# unoedge.net
KiCad netlist of a schematic drawn in EAGLE
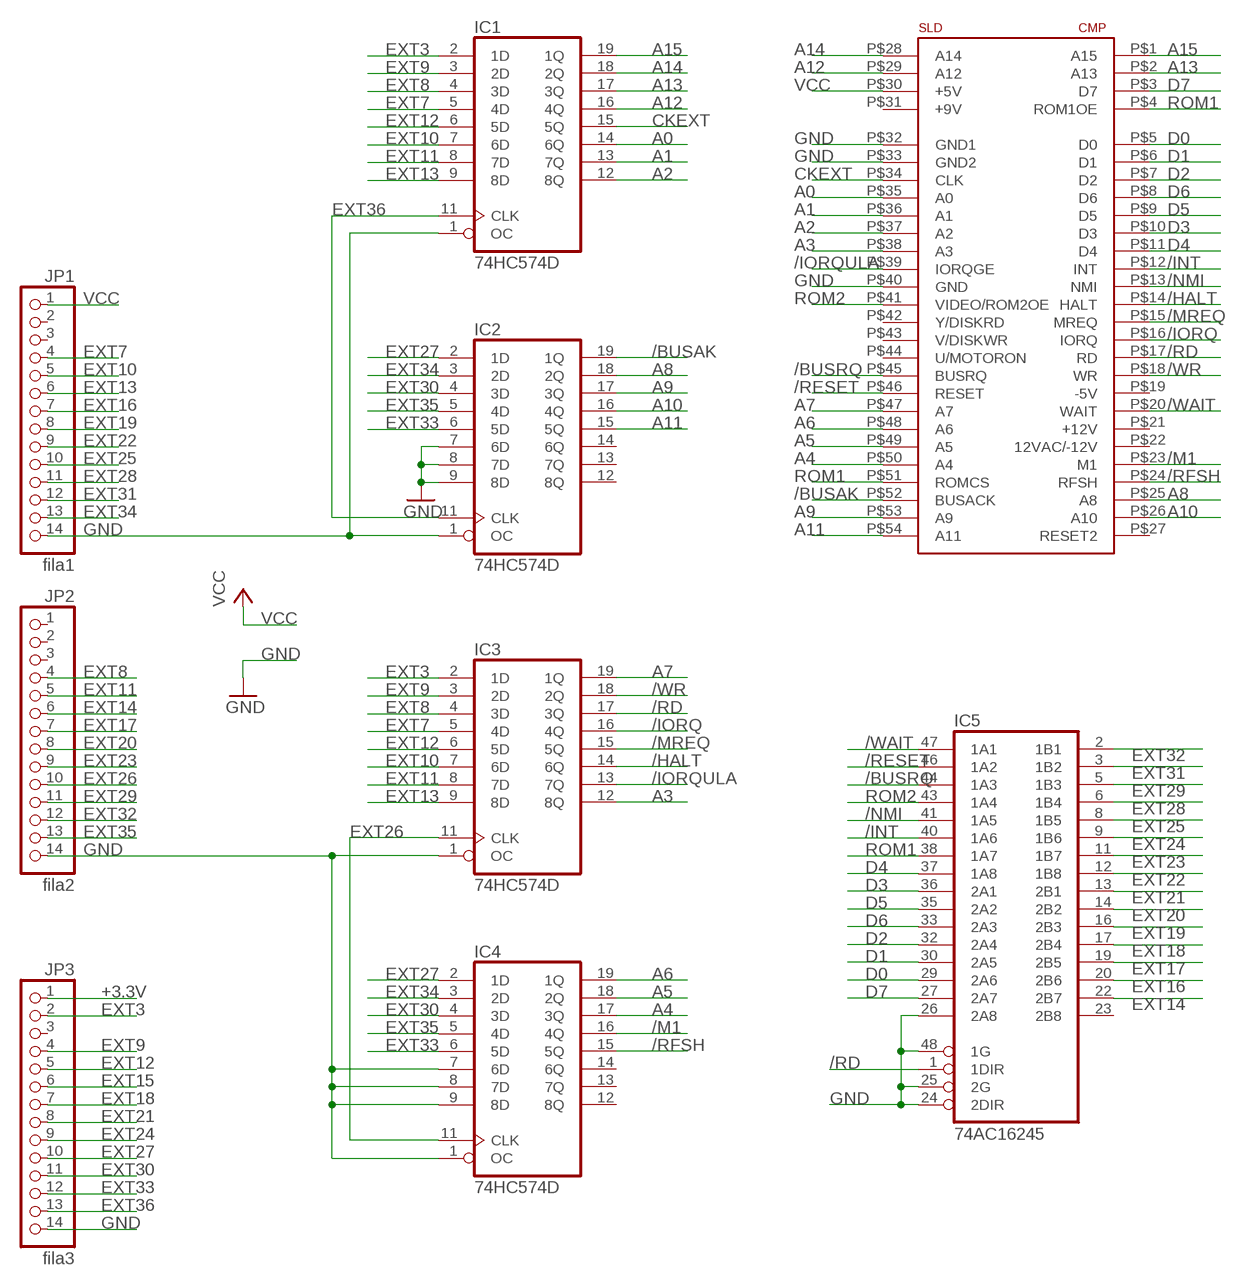
[diagram p0: schematic, sheet 1]

(export (version "E")
  (design (tool "Eeschema 10.0.6"))
  (components
    (comp (ref "IC1")
      (value "74HC574D")
      (footprint "eagle-import:SO20W")
      (libsource (lib "eagle-import") (part "74574DHC"))
    )
    (comp (ref "IC2")
      (value "74HC574D")
      (footprint "eagle-import:SO20W")
      (libsource (lib "eagle-import") (part "74574DHC"))
    )
    (comp (ref "IC3")
      (value "74HC574D")
      (footprint "eagle-import:SO20W")
      (libsource (lib "eagle-import") (part "74574DHC"))
    )
    (comp (ref "IC4")
      (value "74HC574D")
      (footprint "eagle-import:SO20W")
      (libsource (lib "eagle-import") (part "74574DHC"))
    )
    (comp (ref "IC5")
      (value "74AC16245")
      (footprint "eagle-import:SSOP48DL")
      (libsource (lib "eagle-import") (part "74AC16245"))
    )
    (comp (ref "JP1")
      (value "fila1")
      (footprint "eagle-import:1X14")
      (libsource (lib "eagle-import") (part "PINHD-1X14"))
    )
    (comp (ref "JP2")
      (value "fila2")
      (footprint "eagle-import:1X14")
      (libsource (lib "eagle-import") (part "PINHD-1X14"))
    )
    (comp (ref "JP3")
      (value "fila3")
      (footprint "eagle-import:1X14")
      (libsource (lib "eagle-import") (part "PINHD-1X14"))
    )
    (comp (ref "U$2")
      (value "CONECTOR_EDGE_LADO_SPECTRUM")
      (footprint "eagle-import:CONECTOR_LADO_SPECTRUM")
      (libsource (lib "eagle-import") (part "CONECTOR_EDGE_LADO_SPECTRUM"))
    )
  )
  (nets
    (net (code "1") (name "/+3.3V") (class "Default")
      (node (ref "JP3") (pin "1") (pinfunction "1_1") (pintype "passive"))
    )
    (net (code "2") (name "/A0") (class "Default")
      (node (ref "IC1") (pin "14") (pinfunction "6Q_14") (pintype "tri_state"))
      (node (ref "U$2") (pin "P$35") (pinfunction "A0_P$35") (pintype "bidirectional"))
    )
    (net (code "3") (name "/A1") (class "Default")
      (node (ref "IC1") (pin "13") (pinfunction "7Q_13") (pintype "tri_state"))
      (node (ref "U$2") (pin "P$36") (pinfunction "A1_P$36") (pintype "bidirectional"))
    )
    (net (code "4") (name "/A2") (class "Default")
      (node (ref "IC1") (pin "12") (pinfunction "8Q_12") (pintype "tri_state"))
      (node (ref "U$2") (pin "P$37") (pinfunction "A2_P$37") (pintype "bidirectional"))
    )
    (net (code "5") (name "/A3") (class "Default")
      (node (ref "IC3") (pin "12") (pinfunction "8Q_12") (pintype "tri_state"))
      (node (ref "U$2") (pin "P$38") (pinfunction "A3_P$38") (pintype "bidirectional"))
    )
    (net (code "6") (name "/A4") (class "Default")
      (node (ref "IC4") (pin "17") (pinfunction "3Q_17") (pintype "tri_state"))
      (node (ref "U$2") (pin "P$50") (pinfunction "A4_P$50") (pintype "bidirectional"))
    )
    (net (code "7") (name "/A5") (class "Default")
      (node (ref "IC4") (pin "18") (pinfunction "2Q_18") (pintype "tri_state"))
      (node (ref "U$2") (pin "P$49") (pinfunction "A5_P$49") (pintype "bidirectional"))
    )
    (net (code "8") (name "/A6") (class "Default")
      (node (ref "IC4") (pin "19") (pinfunction "1Q_19") (pintype "tri_state"))
      (node (ref "U$2") (pin "P$48") (pinfunction "A6_P$48") (pintype "bidirectional"))
    )
    (net (code "9") (name "/A7") (class "Default")
      (node (ref "IC3") (pin "19") (pinfunction "1Q_19") (pintype "tri_state"))
      (node (ref "U$2") (pin "P$47") (pinfunction "A7_P$47") (pintype "bidirectional"))
    )
    (net (code "10") (name "/A8") (class "Default")
      (node (ref "IC2") (pin "18") (pinfunction "2Q_18") (pintype "tri_state"))
      (node (ref "U$2") (pin "P$25") (pinfunction "A8_P$25") (pintype "bidirectional"))
    )
    (net (code "11") (name "/A9") (class "Default")
      (node (ref "IC2") (pin "17") (pinfunction "3Q_17") (pintype "tri_state"))
      (node (ref "U$2") (pin "P$53") (pinfunction "A9_P$53") (pintype "bidirectional"))
    )
    (net (code "12") (name "/A10") (class "Default")
      (node (ref "IC2") (pin "16") (pinfunction "4Q_16") (pintype "tri_state"))
      (node (ref "U$2") (pin "P$26") (pinfunction "A10_P$26") (pintype "bidirectional"))
    )
    (net (code "13") (name "/A11") (class "Default")
      (node (ref "IC2") (pin "15") (pinfunction "5Q_15") (pintype "tri_state"))
      (node (ref "U$2") (pin "P$54") (pinfunction "A11_P$54") (pintype "bidirectional"))
    )
    (net (code "14") (name "/A12") (class "Default")
      (node (ref "IC1") (pin "16") (pinfunction "4Q_16") (pintype "tri_state"))
      (node (ref "U$2") (pin "P$29") (pinfunction "A12_P$29") (pintype "bidirectional"))
    )
    (net (code "15") (name "/A13") (class "Default")
      (node (ref "IC1") (pin "17") (pinfunction "3Q_17") (pintype "tri_state"))
      (node (ref "U$2") (pin "P$2") (pinfunction "A13_P$2") (pintype "bidirectional"))
    )
    (net (code "16") (name "/A14") (class "Default")
      (node (ref "IC1") (pin "18") (pinfunction "2Q_18") (pintype "tri_state"))
      (node (ref "U$2") (pin "P$28") (pinfunction "A14_P$28") (pintype "bidirectional"))
    )
    (net (code "17") (name "/A15") (class "Default")
      (node (ref "IC1") (pin "19") (pinfunction "1Q_19") (pintype "tri_state"))
      (node (ref "U$2") (pin "P$1") (pinfunction "A15_P$1") (pintype "bidirectional"))
    )
    (net (code "18") (name "/CKEXT") (class "Default")
      (node (ref "IC1") (pin "15") (pinfunction "5Q_15") (pintype "tri_state"))
      (node (ref "U$2") (pin "P$34") (pinfunction "CLK_P$34") (pintype "bidirectional"))
    )
    (net (code "19") (name "/D0") (class "Default")
      (node (ref "IC5") (pin "29") (pinfunction "2A6_29") (pintype "bidirectional"))
      (node (ref "U$2") (pin "P$5") (pinfunction "D0_P$5") (pintype "bidirectional"))
    )
    (net (code "20") (name "/D1") (class "Default")
      (node (ref "IC5") (pin "30") (pinfunction "2A5_30") (pintype "bidirectional"))
      (node (ref "U$2") (pin "P$6") (pinfunction "D1_P$6") (pintype "bidirectional"))
    )
    (net (code "21") (name "/D2") (class "Default")
      (node (ref "IC5") (pin "32") (pinfunction "2A4_32") (pintype "bidirectional"))
      (node (ref "U$2") (pin "P$7") (pinfunction "D2_P$7") (pintype "bidirectional"))
    )
    (net (code "22") (name "/D3") (class "Default")
      (node (ref "IC5") (pin "36") (pinfunction "2A1_36") (pintype "bidirectional"))
      (node (ref "U$2") (pin "P$10") (pinfunction "D3_P$10") (pintype "bidirectional"))
    )
    (net (code "23") (name "/D4") (class "Default")
      (node (ref "IC5") (pin "37") (pinfunction "1A8_37") (pintype "bidirectional"))
      (node (ref "U$2") (pin "P$11") (pinfunction "D4_P$11") (pintype "bidirectional"))
    )
    (net (code "24") (name "/D5") (class "Default")
      (node (ref "IC5") (pin "35") (pinfunction "2A2_35") (pintype "bidirectional"))
      (node (ref "U$2") (pin "P$9") (pinfunction "D5_P$9") (pintype "bidirectional"))
    )
    (net (code "25") (name "/D6") (class "Default")
      (node (ref "IC5") (pin "33") (pinfunction "2A3_33") (pintype "bidirectional"))
      (node (ref "U$2") (pin "P$8") (pinfunction "D6_P$8") (pintype "bidirectional"))
    )
    (net (code "26") (name "/D7") (class "Default")
      (node (ref "IC5") (pin "27") (pinfunction "2A7_27") (pintype "bidirectional"))
      (node (ref "U$2") (pin "P$3") (pinfunction "D7_P$3") (pintype "bidirectional"))
    )
    (net (code "27") (name "/EXT3") (class "Default")
      (node (ref "IC1") (pin "2") (pinfunction "1D_2") (pintype "input"))
      (node (ref "IC3") (pin "2") (pinfunction "1D_2") (pintype "input"))
      (node (ref "JP3") (pin "2") (pinfunction "2_2") (pintype "passive"))
    )
    (net (code "28") (name "/EXT7") (class "Default")
      (node (ref "IC1") (pin "5") (pinfunction "4D_5") (pintype "input"))
      (node (ref "IC3") (pin "5") (pinfunction "4D_5") (pintype "input"))
      (node (ref "JP1") (pin "4") (pinfunction "4_4") (pintype "passive"))
    )
    (net (code "29") (name "/EXT8") (class "Default")
      (node (ref "IC1") (pin "4") (pinfunction "3D_4") (pintype "input"))
      (node (ref "IC3") (pin "4") (pinfunction "3D_4") (pintype "input"))
      (node (ref "JP2") (pin "4") (pinfunction "4_4") (pintype "passive"))
    )
    (net (code "30") (name "/EXT9") (class "Default")
      (node (ref "IC1") (pin "3") (pinfunction "2D_3") (pintype "input"))
      (node (ref "IC3") (pin "3") (pinfunction "2D_3") (pintype "input"))
      (node (ref "JP3") (pin "4") (pinfunction "4_4") (pintype "passive"))
    )
    (net (code "31") (name "/EXT10") (class "Default")
      (node (ref "IC1") (pin "7") (pinfunction "6D_7") (pintype "input"))
      (node (ref "IC3") (pin "7") (pinfunction "6D_7") (pintype "input"))
      (node (ref "JP1") (pin "5") (pinfunction "5_5") (pintype "passive"))
    )
    (net (code "32") (name "/EXT11") (class "Default")
      (node (ref "IC1") (pin "8") (pinfunction "7D_8") (pintype "input"))
      (node (ref "IC3") (pin "8") (pinfunction "7D_8") (pintype "input"))
      (node (ref "JP2") (pin "5") (pinfunction "5_5") (pintype "passive"))
    )
    (net (code "33") (name "/EXT12") (class "Default")
      (node (ref "IC1") (pin "6") (pinfunction "5D_6") (pintype "input"))
      (node (ref "IC3") (pin "6") (pinfunction "5D_6") (pintype "input"))
      (node (ref "JP3") (pin "5") (pinfunction "5_5") (pintype "passive"))
    )
    (net (code "34") (name "/EXT13") (class "Default")
      (node (ref "IC1") (pin "9") (pinfunction "8D_9") (pintype "input"))
      (node (ref "IC3") (pin "9") (pinfunction "8D_9") (pintype "input"))
      (node (ref "JP1") (pin "6") (pinfunction "6_6") (pintype "passive"))
    )
    (net (code "35") (name "/EXT14") (class "Default")
      (node (ref "IC5") (pin "22") (pinfunction "2B7_22") (pintype "bidirectional"))
      (node (ref "JP2") (pin "6") (pinfunction "6_6") (pintype "passive"))
    )
    (net (code "36") (name "/EXT15") (class "Default")
      (node (ref "JP3") (pin "6") (pinfunction "6_6") (pintype "passive"))
    )
    (net (code "37") (name "/EXT16") (class "Default")
      (node (ref "IC5") (pin "20") (pinfunction "2B6_20") (pintype "bidirectional"))
      (node (ref "JP1") (pin "7") (pinfunction "7_7") (pintype "passive"))
    )
    (net (code "38") (name "/EXT17") (class "Default")
      (node (ref "IC5") (pin "19") (pinfunction "2B5_19") (pintype "bidirectional"))
      (node (ref "JP2") (pin "7") (pinfunction "7_7") (pintype "passive"))
    )
    (net (code "39") (name "/EXT18") (class "Default")
      (node (ref "IC5") (pin "17") (pinfunction "2B4_17") (pintype "bidirectional"))
      (node (ref "JP3") (pin "7") (pinfunction "7_7") (pintype "passive"))
    )
    (net (code "40") (name "/EXT19") (class "Default")
      (node (ref "IC5") (pin "16") (pinfunction "2B3_16") (pintype "bidirectional"))
      (node (ref "JP1") (pin "8") (pinfunction "8_8") (pintype "passive"))
    )
    (net (code "41") (name "/EXT20") (class "Default")
      (node (ref "IC5") (pin "14") (pinfunction "2B2_14") (pintype "bidirectional"))
      (node (ref "JP2") (pin "8") (pinfunction "8_8") (pintype "passive"))
    )
    (net (code "42") (name "/EXT21") (class "Default")
      (node (ref "IC5") (pin "13") (pinfunction "2B1_13") (pintype "bidirectional"))
      (node (ref "JP3") (pin "8") (pinfunction "8_8") (pintype "passive"))
    )
    (net (code "43") (name "/EXT22") (class "Default")
      (node (ref "IC5") (pin "12") (pinfunction "1B8_12") (pintype "bidirectional"))
      (node (ref "JP1") (pin "9") (pinfunction "9_9") (pintype "passive"))
    )
    (net (code "44") (name "/EXT23") (class "Default")
      (node (ref "IC5") (pin "11") (pinfunction "1B7_11") (pintype "bidirectional"))
      (node (ref "JP2") (pin "9") (pinfunction "9_9") (pintype "passive"))
    )
    (net (code "45") (name "/EXT24") (class "Default")
      (node (ref "IC5") (pin "9") (pinfunction "1B6_9") (pintype "bidirectional"))
      (node (ref "JP3") (pin "9") (pinfunction "9_9") (pintype "passive"))
    )
    (net (code "46") (name "/EXT25") (class "Default")
      (node (ref "IC5") (pin "8") (pinfunction "1B5_8") (pintype "bidirectional"))
      (node (ref "JP1") (pin "10") (pinfunction "10_10") (pintype "passive"))
    )
    (net (code "47") (name "/EXT26") (class "Default")
      (node (ref "IC3") (pin "11") (pinfunction "CLK_11") (pintype "input"))
      (node (ref "IC4") (pin "11") (pinfunction "CLK_11") (pintype "input"))
      (node (ref "JP2") (pin "10") (pinfunction "10_10") (pintype "passive"))
    )
    (net (code "48") (name "/EXT27") (class "Default")
      (node (ref "IC2") (pin "2") (pinfunction "1D_2") (pintype "input"))
      (node (ref "IC4") (pin "2") (pinfunction "1D_2") (pintype "input"))
      (node (ref "JP3") (pin "10") (pinfunction "10_10") (pintype "passive"))
    )
    (net (code "49") (name "/EXT28") (class "Default")
      (node (ref "IC5") (pin "6") (pinfunction "1B4_6") (pintype "bidirectional"))
      (node (ref "JP1") (pin "11") (pinfunction "11_11") (pintype "passive"))
    )
    (net (code "50") (name "/EXT29") (class "Default")
      (node (ref "IC5") (pin "5") (pinfunction "1B3_5") (pintype "bidirectional"))
      (node (ref "JP2") (pin "11") (pinfunction "11_11") (pintype "passive"))
    )
    (net (code "51") (name "/EXT30") (class "Default")
      (node (ref "IC2") (pin "4") (pinfunction "3D_4") (pintype "input"))
      (node (ref "IC4") (pin "4") (pinfunction "3D_4") (pintype "input"))
      (node (ref "JP3") (pin "11") (pinfunction "11_11") (pintype "passive"))
    )
    (net (code "52") (name "/EXT31") (class "Default")
      (node (ref "IC5") (pin "3") (pinfunction "1B2_3") (pintype "bidirectional"))
      (node (ref "JP1") (pin "12") (pinfunction "12_12") (pintype "passive"))
    )
    (net (code "53") (name "/EXT32") (class "Default")
      (node (ref "IC5") (pin "2") (pinfunction "1B1_2") (pintype "bidirectional"))
      (node (ref "JP2") (pin "12") (pinfunction "12_12") (pintype "passive"))
    )
    (net (code "54") (name "/EXT33") (class "Default")
      (node (ref "IC2") (pin "6") (pinfunction "5D_6") (pintype "input"))
      (node (ref "IC4") (pin "6") (pinfunction "5D_6") (pintype "input"))
      (node (ref "JP3") (pin "12") (pinfunction "12_12") (pintype "passive"))
    )
    (net (code "55") (name "/EXT34") (class "Default")
      (node (ref "IC2") (pin "3") (pinfunction "2D_3") (pintype "input"))
      (node (ref "IC4") (pin "3") (pinfunction "2D_3") (pintype "input"))
      (node (ref "JP1") (pin "13") (pinfunction "13_13") (pintype "passive"))
    )
    (net (code "56") (name "/EXT35") (class "Default")
      (node (ref "IC2") (pin "5") (pinfunction "4D_5") (pintype "input"))
      (node (ref "IC4") (pin "5") (pinfunction "4D_5") (pintype "input"))
      (node (ref "JP2") (pin "13") (pinfunction "13_13") (pintype "passive"))
    )
    (net (code "57") (name "/EXT36") (class "Default")
      (node (ref "IC1") (pin "11") (pinfunction "CLK_11") (pintype "input"))
      (node (ref "IC2") (pin "11") (pinfunction "CLK_11") (pintype "input"))
      (node (ref "JP3") (pin "13") (pinfunction "13_13") (pintype "passive"))
    )
    (net (code "58") (name "/ROM1") (class "Default")
      (node (ref "IC5") (pin "38") (pinfunction "1A7_38") (pintype "bidirectional"))
      (node (ref "U$2") (pin "P$4") (pinfunction "ROM1OE_P$4") (pintype "bidirectional"))
      (node (ref "U$2") (pin "P$51") (pinfunction "ROMCS_P$51") (pintype "bidirectional"))
    )
    (net (code "59") (name "/ROM2") (class "Default")
      (node (ref "IC5") (pin "43") (pinfunction "1A4_43") (pintype "bidirectional"))
      (node (ref "U$2") (pin "P$41") (pinfunction "VIDEO/ROM2OE_P$41") (pintype "bidirectional"))
    )
    (net (code "60") (name "/{slash}BUSAK") (class "Default")
      (node (ref "IC2") (pin "19") (pinfunction "1Q_19") (pintype "tri_state"))
      (node (ref "U$2") (pin "P$52") (pinfunction "BUSACK_P$52") (pintype "bidirectional"))
    )
    (net (code "61") (name "/{slash}BUSRQ") (class "Default")
      (node (ref "IC5") (pin "44") (pinfunction "1A3_44") (pintype "bidirectional"))
      (node (ref "U$2") (pin "P$45") (pinfunction "BUSRQ_P$45") (pintype "bidirectional"))
    )
    (net (code "62") (name "/{slash}HALT") (class "Default")
      (node (ref "IC3") (pin "14") (pinfunction "6Q_14") (pintype "tri_state"))
      (node (ref "U$2") (pin "P$14") (pinfunction "HALT_P$14") (pintype "bidirectional"))
    )
    (net (code "63") (name "/{slash}INT") (class "Default")
      (node (ref "IC5") (pin "40") (pinfunction "1A6_40") (pintype "bidirectional"))
      (node (ref "U$2") (pin "P$12") (pinfunction "INT_P$12") (pintype "bidirectional"))
    )
    (net (code "64") (name "/{slash}IORQ") (class "Default")
      (node (ref "IC3") (pin "16") (pinfunction "4Q_16") (pintype "tri_state"))
      (node (ref "U$2") (pin "P$16") (pinfunction "IORQ_P$16") (pintype "bidirectional"))
    )
    (net (code "65") (name "/{slash}IORQULA") (class "Default")
      (node (ref "IC3") (pin "13") (pinfunction "7Q_13") (pintype "tri_state"))
      (node (ref "U$2") (pin "P$39") (pinfunction "IORQGE_P$39") (pintype "bidirectional"))
    )
    (net (code "66") (name "/{slash}M1") (class "Default")
      (node (ref "IC4") (pin "16") (pinfunction "4Q_16") (pintype "tri_state"))
      (node (ref "U$2") (pin "P$23") (pinfunction "M1_P$23") (pintype "bidirectional"))
    )
    (net (code "67") (name "/{slash}MREQ") (class "Default")
      (node (ref "IC3") (pin "15") (pinfunction "5Q_15") (pintype "tri_state"))
      (node (ref "U$2") (pin "P$15") (pinfunction "MREQ_P$15") (pintype "bidirectional"))
    )
    (net (code "68") (name "/{slash}NMI") (class "Default")
      (node (ref "IC5") (pin "41") (pinfunction "1A5_41") (pintype "bidirectional"))
      (node (ref "U$2") (pin "P$13") (pinfunction "NMI_P$13") (pintype "bidirectional"))
    )
    (net (code "69") (name "/{slash}RD") (class "Default")
      (node (ref "IC3") (pin "17") (pinfunction "3Q_17") (pintype "tri_state"))
      (node (ref "IC5") (pin "1") (pinfunction "1DIR_1") (pintype "input"))
      (node (ref "U$2") (pin "P$17") (pinfunction "RD_P$17") (pintype "bidirectional"))
    )
    (net (code "70") (name "/{slash}RESET") (class "Default")
      (node (ref "IC5") (pin "46") (pinfunction "1A2_46") (pintype "bidirectional"))
      (node (ref "U$2") (pin "P$46") (pinfunction "RESET_P$46") (pintype "bidirectional"))
    )
    (net (code "71") (name "/{slash}RFSH") (class "Default")
      (node (ref "IC4") (pin "15") (pinfunction "5Q_15") (pintype "tri_state"))
      (node (ref "U$2") (pin "P$24") (pinfunction "RFSH_P$24") (pintype "bidirectional"))
    )
    (net (code "72") (name "/{slash}WAIT") (class "Default")
      (node (ref "IC5") (pin "47") (pinfunction "1A1_47") (pintype "bidirectional"))
      (node (ref "U$2") (pin "P$20") (pinfunction "WAIT_P$20") (pintype "bidirectional"))
    )
    (net (code "73") (name "/{slash}WR") (class "Default")
      (node (ref "IC3") (pin "18") (pinfunction "2Q_18") (pintype "tri_state"))
      (node (ref "U$2") (pin "P$18") (pinfunction "WR_P$18") (pintype "bidirectional"))
    )
    (net (code "74") (name "GND") (class "Default")
      (node (ref "IC1") (pin "1") (pinfunction "OC_1") (pintype "input"))
      (node (ref "IC2") (pin "1") (pinfunction "OC_1") (pintype "input"))
      (node (ref "IC2") (pin "7") (pinfunction "6D_7") (pintype "input"))
      (node (ref "IC2") (pin "8") (pinfunction "7D_8") (pintype "input"))
      (node (ref "IC2") (pin "9") (pinfunction "8D_9") (pintype "input"))
      (node (ref "IC3") (pin "1") (pinfunction "OC_1") (pintype "input"))
      (node (ref "IC4") (pin "1") (pinfunction "OC_1") (pintype "input"))
      (node (ref "IC4") (pin "7") (pinfunction "6D_7") (pintype "input"))
      (node (ref "IC4") (pin "8") (pinfunction "7D_8") (pintype "input"))
      (node (ref "IC4") (pin "9") (pinfunction "8D_9") (pintype "input"))
      (node (ref "IC5") (pin "24") (pinfunction "2DIR_24") (pintype "input"))
      (node (ref "IC5") (pin "25") (pinfunction "2G_25") (pintype "input"))
      (node (ref "IC5") (pin "26") (pinfunction "2A8_26") (pintype "bidirectional"))
      (node (ref "IC5") (pin "48") (pinfunction "1G_48") (pintype "input"))
      (node (ref "JP1") (pin "14") (pinfunction "14_14") (pintype "passive"))
      (node (ref "JP2") (pin "14") (pinfunction "14_14") (pintype "passive"))
      (node (ref "JP3") (pin "14") (pinfunction "14_14") (pintype "passive"))
      (node (ref "U$2") (pin "P$32") (pinfunction "GND1_P$32") (pintype "bidirectional"))
      (node (ref "U$2") (pin "P$33") (pinfunction "GND2_P$33") (pintype "bidirectional"))
      (node (ref "U$2") (pin "P$40") (pinfunction "GND_P$40") (pintype "bidirectional"))
    )
    (net (code "75") (name "VCC") (class "Default")
      (node (ref "JP1") (pin "1") (pinfunction "1_1") (pintype "passive"))
      (node (ref "U$2") (pin "P$30") (pinfunction "+5V_P$30") (pintype "bidirectional"))
    )
    (net (code "76") (name "unconnected-(IC2A-6Q-Pad14)") (class "Default")
      (node (ref "IC2") (pin "14") (pinfunction "6Q_14") (pintype "tri_state"))
    )
    (net (code "77") (name "unconnected-(IC2A-7Q-Pad13)") (class "Default")
      (node (ref "IC2") (pin "13") (pinfunction "7Q_13") (pintype "tri_state"))
    )
    (net (code "78") (name "unconnected-(IC2A-8Q-Pad12)") (class "Default")
      (node (ref "IC2") (pin "12") (pinfunction "8Q_12") (pintype "tri_state"))
    )
    (net (code "79") (name "unconnected-(IC4A-6Q-Pad14)") (class "Default")
      (node (ref "IC4") (pin "14") (pinfunction "6Q_14") (pintype "tri_state"))
    )
    (net (code "80") (name "unconnected-(IC4A-7Q-Pad13)") (class "Default")
      (node (ref "IC4") (pin "13") (pinfunction "7Q_13") (pintype "tri_state"))
    )
    (net (code "81") (name "unconnected-(IC4A-8Q-Pad12)") (class "Default")
      (node (ref "IC4") (pin "12") (pinfunction "8Q_12") (pintype "tri_state"))
    )
    (net (code "82") (name "unconnected-(IC5A-2B8-Pad23)") (class "Default")
      (node (ref "IC5") (pin "23") (pinfunction "2B8_23") (pintype "bidirectional"))
    )
    (net (code "83") (name "unconnected-(JP1-Pad2)") (class "Default")
      (node (ref "JP1") (pin "2") (pinfunction "2_2") (pintype "passive"))
    )
    (net (code "84") (name "unconnected-(JP1-Pad3)") (class "Default")
      (node (ref "JP1") (pin "3") (pinfunction "3_3") (pintype "passive"))
    )
    (net (code "85") (name "unconnected-(JP2-Pad1)") (class "Default")
      (node (ref "JP2") (pin "1") (pinfunction "1_1") (pintype "passive"))
    )
    (net (code "86") (name "unconnected-(JP2-Pad2)") (class "Default")
      (node (ref "JP2") (pin "2") (pinfunction "2_2") (pintype "passive"))
    )
    (net (code "87") (name "unconnected-(JP2-Pad3)") (class "Default")
      (node (ref "JP2") (pin "3") (pinfunction "3_3") (pintype "passive"))
    )
    (net (code "88") (name "unconnected-(JP3-Pad3)") (class "Default")
      (node (ref "JP3") (pin "3") (pinfunction "3_3") (pintype "passive"))
    )
    (net (code "89") (name "unconnected-(U$2-+9V-PadP$31)") (class "Default")
      (node (ref "U$2") (pin "P$31") (pinfunction "+9V_P$31") (pintype "bidirectional"))
    )
    (net (code "90") (name "unconnected-(U$2-+12V-PadP$21)") (class "Default")
      (node (ref "U$2") (pin "P$21") (pinfunction "+12V_P$21") (pintype "bidirectional"))
    )
    (net (code "91") (name "unconnected-(U$2--5V-PadP$19)") (class "Default")
      (node (ref "U$2") (pin "P$19") (pinfunction "-5V_P$19") (pintype "bidirectional"))
    )
    (net (code "92") (name "unconnected-(U$2-12VAC{slash}-12V-PadP$22)") (class "Default")
      (node (ref "U$2") (pin "P$22") (pinfunction "12VAC/-12V_P$22") (pintype "bidirectional"))
    )
    (net (code "93") (name "unconnected-(U$2-RESET2-PadP$27)") (class "Default")
      (node (ref "U$2") (pin "P$27") (pinfunction "RESET2_P$27") (pintype "bidirectional"))
    )
    (net (code "94") (name "unconnected-(U$2-U{slash}MOTORON-PadP$44)") (class "Default")
      (node (ref "U$2") (pin "P$44") (pinfunction "U/MOTORON_P$44") (pintype "bidirectional"))
    )
    (net (code "95") (name "unconnected-(U$2-V{slash}DISKWR-PadP$43)") (class "Default")
      (node (ref "U$2") (pin "P$43") (pinfunction "V/DISKWR_P$43") (pintype "bidirectional"))
    )
    (net (code "96") (name "unconnected-(U$2-Y{slash}DISKRD-PadP$42)") (class "Default")
      (node (ref "U$2") (pin "P$42") (pinfunction "Y/DISKRD_P$42") (pintype "bidirectional"))
    )
  )
)
